# Relay.net
KiCad netlist of a schematic drawn in Altium Designer
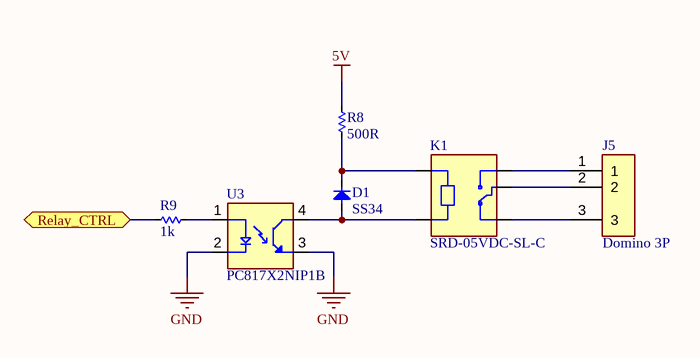
[diagram p0: Relay.SchDoc]

(export (version "E")
  (design (tool "Eeschema 10.0.6"))
  (components
    (comp (ref "D1")
      (value "SS34")
      (footprint "DO-214AC_SMA")
      (description "Default Diode")
      (fields (field (name "PUBLISHER") "Altium Limited"))
      (libsource (lib "BTL_SCHLIB") (part "Diode SMD"))
    )
    (comp (ref "J5")
      (value "Domino 3P")
      (footprint "Terminal Domino 3P")
      (libsource (lib "BTL_SCHLIB") (part "Domino 3P"))
    )
    (comp (ref "K1")
      (value "SRD-05VDC-SL-C")
      (footprint "RELAY_SRD-05VDC-SL-C")
      (fields (field (name "MF") "Songle Relay"))
      (libsource (lib "BTL_SCHLIB") (part "SRD-05VDC-SL-C"))
    )
    (comp (ref "R8")
      (value "500R")
      (footprint "RES_C_1608X60")
      (description "RES")
      (libsource (lib "BTL_SCHLIB") (part "RES_SMD"))
    )
    (comp (ref "R9")
      (value "1k")
      (footprint "RES_C_1608X60")
      (description "RES")
      (libsource (lib "BTL_SCHLIB") (part "RES_SMD"))
    )
    (comp (ref "U3")
      (value "PC817X2NIP1B")
      (footprint "SOIC254P960X420-4N")
      (description "Optocoupler DC-IN 1-CH Transistor DC-OUT 4-Pin DIP SMD T/R")
      (fields (field (name "MF") "Sharp Microelectronics"))
      (libsource (lib "BTL_SCHLIB") (part "PC817X2NIP1B"))
    )
  )
  (nets
    (net (code "1") (name "/Relay_CTRL") (class "Default")
      (node (ref "R9") (pin "1") (pinfunction "1_1") (pintype "passive"))
    )
    (net (code "2") (name "5V") (class "Default")
      (node (ref "R8") (pin "2") (pinfunction "2_2") (pintype "passive"))
    )
    (net (code "3") (name "GND") (class "Default")
      (node (ref "U3") (pin "2") (pinfunction "C_2") (pintype "passive"))
      (node (ref "U3") (pin "3") (pinfunction "ET_3") (pintype "passive"))
    )
    (net (code "4") (name "Net-(D1-A)") (class "Default")
      (node (ref "D1") (pin "2") (pinfunction "A_2") (pintype "passive"))
      (node (ref "K1") (pin "A2") (pinfunction "A2_A2") (pintype "passive"))
      (node (ref "U3") (pin "4") (pinfunction "CT_4") (pintype "passive"))
    )
    (net (code "5") (name "Net-(D1-K)") (class "Default")
      (node (ref "D1") (pin "1") (pinfunction "K_1") (pintype "passive"))
      (node (ref "K1") (pin "A1") (pinfunction "A1_A1") (pintype "passive"))
      (node (ref "R8") (pin "1") (pinfunction "1_1") (pintype "passive"))
    )
    (net (code "6") (name "Net-(J5-Pad1)") (class "Default")
      (node (ref "J5") (pin "1") (pinfunction "1_1") (pintype "passive"))
      (node (ref "K1") (pin "NO") (pinfunction "NO_NO") (pintype "passive"))
    )
    (net (code "7") (name "Net-(J5-Pad2)") (class "Default")
      (node (ref "J5") (pin "2") (pinfunction "2_2") (pintype "passive"))
      (node (ref "K1") (pin "COM") (pinfunction "COM_COM") (pintype "passive"))
    )
    (net (code "8") (name "Net-(J5-Pad3)") (class "Default")
      (node (ref "J5") (pin "3") (pinfunction "3_3") (pintype "passive"))
      (node (ref "K1") (pin "NC") (pinfunction "NC_NC") (pintype "passive"))
    )
    (net (code "9") (name "Net-(U3-A)") (class "Default")
      (node (ref "R9") (pin "2") (pinfunction "2_2") (pintype "passive"))
      (node (ref "U3") (pin "1") (pinfunction "A_1") (pintype "passive"))
    )
  )
)
